# WiREDSchema.net
KiCad netlist of a schematic drawn in EAGLE
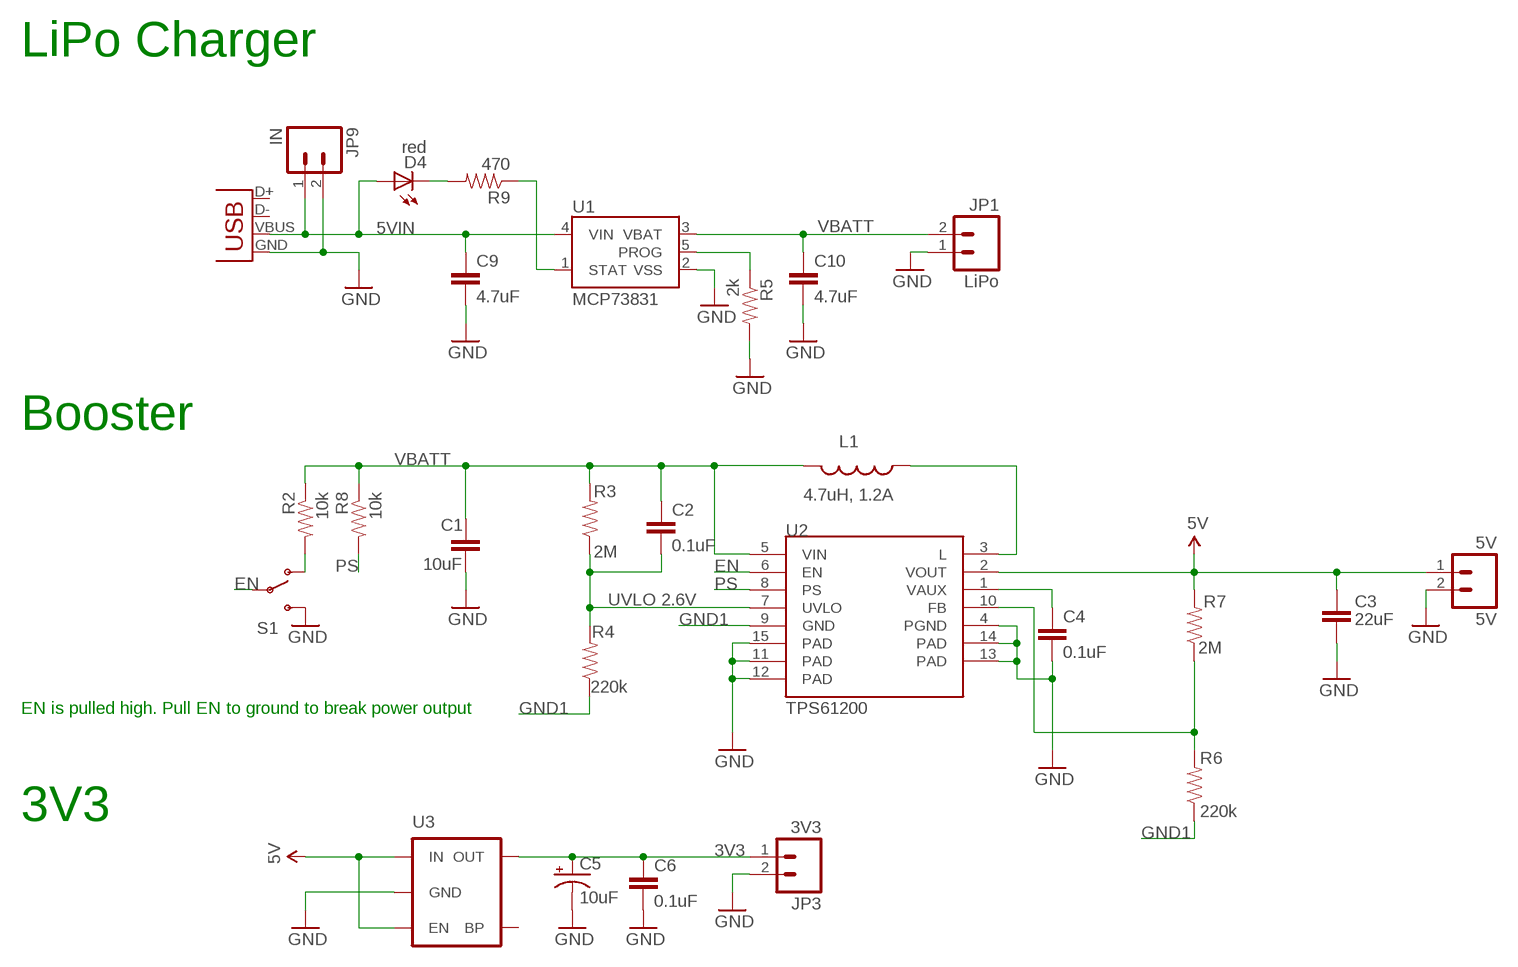
[diagram p0: schematic, sheet 1]

(export (version "E")
  (design (tool "Eeschema 10.0.6"))
  (components
    (comp (ref "5V")
      (value "5V")
      (footprint "eagle-import:1X02")
      (libsource (lib "eagle-import") (part "M02PTH"))
    )
    (comp (ref "C1")
      (value "10uF")
      (footprint "eagle-import:1206")
      (fields (field (name "MF") "AVX") (field (name "MPN") "12066D106KAT2A"))
      (libsource (lib "eagle-import") (part "CAP1206"))
    )
    (comp (ref "C2")
      (value "0.1uF")
      (footprint "eagle-import:0402-CAP")
      (fields (field (name "MF") "AVX") (field (name "MPN") "04026D104KAT2A"))
      (libsource (lib "eagle-import") (part "CAP0402-CAP"))
    )
    (comp (ref "C3")
      (value "22uF")
      (footprint "eagle-import:0805")
      (fields (field (name "MF") "KEMET") (field (name "MPN") "C0805C226M9PACTU"))
      (libsource (lib "eagle-import") (part "CAP0805"))
    )
    (comp (ref "C4")
      (value "0.1uF")
      (footprint "eagle-import:0402-CAP")
      (fields (field (name "MF") "AVX") (field (name "MPN") "04026D104KAT2A"))
      (libsource (lib "eagle-import") (part "CAP0402-CAP"))
    )
    (comp (ref "C5")
      (value "10uF")
      (footprint "eagle-import:EIA3216")
      (fields (field (name "MF") "AVX") (field (name "MPN") "TAJA106K006RNJ"))
      (libsource (lib "eagle-import") (part "10UF-16V-10%(TANT)"))
    )
    (comp (ref "C6")
      (value "0.1uF")
      (footprint "eagle-import:0402-CAP")
      (fields (field (name "MF") "AVX") (field (name "MPN") "04026D104KAT2A"))
      (libsource (lib "eagle-import") (part "CAP0402-CAP"))
    )
    (comp (ref "C9")
      (value "4.7uF")
      (footprint "eagle-import:0402-CAP")
      (fields (field (name "MF") "TAIYO YUDEN") (field (name "MPN") "JMK105BBJ475MV-F"))
      (libsource (lib "eagle-import") (part "CAP0402-CAP"))
    )
    (comp (ref "C10")
      (value "4.7uF")
      (footprint "eagle-import:0402-CAP")
      (fields (field (name "MF") "TAIYO YUDEN") (field (name "MPN") "JMK105BBJ475MV-F"))
      (libsource (lib "eagle-import") (part "CAP0402-CAP"))
    )
    (comp (ref "D4")
      (value "red")
      (footprint "eagle-import:LED-0603")
      (fields (field (name "MF") "VISHAY") (field (name "MPN") "TLMS1100-GS08."))
      (libsource (lib "eagle-import") (part "LED0603"))
    )
    (comp (ref "JP1")
      (value "LiPo")
      (footprint "eagle-import:JST-2-SMD")
      (libsource (lib "eagle-import") (part "M02-JST-2MM-SMT"))
    )
    (comp (ref "JP3")
      (value "3V3")
      (footprint "eagle-import:1X02")
      (libsource (lib "eagle-import") (part "M02PTH"))
    )
    (comp (ref "JP9")
      (value "IN")
      (footprint "eagle-import:1X02")
      (libsource (lib "eagle-import") (part "M02PTH"))
    )
    (comp (ref "L1")
      (value "4.7uH, 1.2A")
      (footprint "eagle-import:CDRH2D09")
      (fields (field (name "MF") "BOURNS") (field (name "MPN") "SRR4011-4R7YL"))
      (libsource (lib "eagle-import") (part "INDUCTOR."))
    )
    (comp (ref "R2")
      (value "10k")
      (footprint "eagle-import:0402-RES")
      (fields (field (name "MF") "TE CONNECTIVITY") (field (name "MPN") "CRG0402J10K"))
      (libsource (lib "eagle-import") (part "RESISTOR0402-RES"))
    )
    (comp (ref "R3")
      (value "2M")
      (footprint "eagle-import:0402-RES")
      (fields (field (name "MF") "PANASONIC") (field (name "MPN") "ERJ2GEJ205X"))
      (libsource (lib "eagle-import") (part "RESISTOR0402-RES"))
    )
    (comp (ref "R4")
      (value "220k")
      (footprint "eagle-import:0402-RES")
      (fields (field (name "MF") "PANASONIC") (field (name "MPN") "ERJ2GEJ224X"))
      (libsource (lib "eagle-import") (part "RESISTOR0402-RES"))
    )
    (comp (ref "R5")
      (value "2k")
      (footprint "eagle-import:0402-RES")
      (fields (field (name "MF") "PANASONIC") (field (name "MPN") "ERJ2RKF2001X"))
      (libsource (lib "eagle-import") (part "RESISTOR0402-RES"))
    )
    (comp (ref "R6")
      (value "220k")
      (footprint "eagle-import:0402-RES")
      (fields (field (name "MF") "PANASONIC") (field (name "MPN") "ERJ2GEJ224X"))
      (libsource (lib "eagle-import") (part "RESISTOR0402-RES"))
    )
    (comp (ref "R7")
      (value "2M")
      (footprint "eagle-import:0402-RES")
      (fields (field (name "MF") "PANASONIC") (field (name "MPN") "ERJ2GEJ205X"))
      (libsource (lib "eagle-import") (part "RESISTOR0402-RES"))
    )
    (comp (ref "R8")
      (value "10k")
      (footprint "eagle-import:0402-RES")
      (fields (field (name "MF") "TE CONNECTIVITY") (field (name "MPN") "CRG0402J10K"))
      (libsource (lib "eagle-import") (part "RESISTOR0402-RES"))
    )
    (comp (ref "R9")
      (value "470")
      (footprint "eagle-import:0402-RES")
      (fields (field (name "MF") "TE CONNECTIVITY") (field (name "MPN") "CRG0402F470R"))
      (libsource (lib "eagle-import") (part "RESISTOR0402-RES"))
    )
    (comp (ref "S1")
      (value "SWITCH-SPDTSMD")
      (footprint "eagle-import:AYZ0202")
      (libsource (lib "eagle-import") (part "SWITCH-SPDTSMD"))
    )
    (comp (ref "U1")
      (value "MCP73831")
      (footprint "eagle-import:SOT23-5")
      (fields (field (name "MF") "MICROCHIP") (field (name "MPN") "MCP73831T-2ACI/OT"))
      (libsource (lib "eagle-import") (part "MCP73831"))
    )
    (comp (ref "U2")
      (value "TPS61200")
      (footprint "eagle-import:QFN-10_PAD")
      (fields (field (name "MF") "TEXAS INSTRUMENTS") (field (name "MPN") "TPS61200DRCTG4"))
      (libsource (lib "eagle-import") (part "TPS61200"))
    )
    (comp (ref "U3")
      (value "MIC52053.3V")
      (footprint "eagle-import:SOT23-5")
      (fields (field (name "MF") "MICREL SEMICONDUCTOR") (field (name "MPN") "MIC5205YM5 TR"))
      (libsource (lib "eagle-import") (part "MIC52053.3V"))
    )
    (comp (ref "X1")
      (value "USB-MICROB")
      (footprint "eagle-import:USB-MICROB")
      (libsource (lib "eagle-import") (part "USB-MICROB"))
    )
  )
  (nets
    (net (code "1") (name "/3V3") (class "Default")
      (node (ref "C5") (pin "A") (pinfunction "+_A") (pintype "passive"))
      (node (ref "C6") (pin "1") (pinfunction "1_1") (pintype "passive"))
      (node (ref "JP3") (pin "1") (pinfunction "1_1") (pintype "passive"))
      (node (ref "U3") (pin "5") (pinfunction "OUT_5") (pintype "passive"))
    )
    (net (code "2") (name "/5VIN") (class "Default")
      (node (ref "C9") (pin "1") (pinfunction "1_1") (pintype "passive"))
      (node (ref "D4") (pin "A") (pinfunction "A_A") (pintype "passive"))
      (node (ref "JP9") (pin "1") (pinfunction "1_1") (pintype "passive"))
      (node (ref "U1") (pin "4") (pinfunction "VIN_4") (pintype "power_in"))
      (node (ref "X1") (pin "VBUS") (pinfunction "VBUS_VBUS") (pintype "bidirectional"))
    )
    (net (code "3") (name "/EN") (class "Default")
      (node (ref "S1") (pin "2") (pinfunction "P_2") (pintype "passive"))
      (node (ref "U2") (pin "6") (pinfunction "EN_6") (pintype "input"))
    )
    (net (code "4") (name "/GND1") (class "Default")
      (node (ref "R4") (pin "1") (pinfunction "1_1") (pintype "passive"))
      (node (ref "R6") (pin "1") (pinfunction "1_1") (pintype "passive"))
      (node (ref "U2") (pin "9") (pinfunction "GND_9") (pintype "power_in"))
    )
    (net (code "5") (name "/PS") (class "Default")
      (node (ref "R8") (pin "2") (pinfunction "2_2") (pintype "passive"))
      (node (ref "U2") (pin "8") (pinfunction "PS_8") (pintype "input"))
    )
    (net (code "6") (name "/VBATT") (class "Default")
      (node (ref "C1") (pin "1") (pinfunction "1_1") (pintype "passive"))
      (node (ref "C10") (pin "1") (pinfunction "1_1") (pintype "passive"))
      (node (ref "C2") (pin "1") (pinfunction "1_1") (pintype "passive"))
      (node (ref "JP1") (pin "2") (pinfunction "2_2") (pintype "passive"))
      (node (ref "L1") (pin "P$2") (pinfunction "2_P$2") (pintype "passive"))
      (node (ref "R2") (pin "1") (pinfunction "1_1") (pintype "passive"))
      (node (ref "R3") (pin "2") (pinfunction "2_2") (pintype "passive"))
      (node (ref "R8") (pin "1") (pinfunction "1_1") (pintype "passive"))
      (node (ref "U1") (pin "3") (pinfunction "VBAT_3") (pintype "power_in"))
      (node (ref "U2") (pin "5") (pinfunction "VIN_5") (pintype "power_in"))
    )
    (net (code "7") (name "5V") (class "Default")
      (node (ref "5V") (pin "1") (pinfunction "1_1") (pintype "passive"))
      (node (ref "C3") (pin "1") (pinfunction "1_1") (pintype "passive"))
      (node (ref "R7") (pin "2") (pinfunction "2_2") (pintype "passive"))
      (node (ref "U2") (pin "2") (pinfunction "VOUT_2") (pintype "passive"))
      (node (ref "U3") (pin "1") (pinfunction "IN_1") (pintype "input"))
      (node (ref "U3") (pin "3") (pinfunction "EN_3") (pintype "input"))
    )
    (net (code "8") (name "GND") (class "Default")
      (node (ref "5V") (pin "2") (pinfunction "2_2") (pintype "passive"))
      (node (ref "C1") (pin "2") (pinfunction "2_2") (pintype "passive"))
      (node (ref "C10") (pin "2") (pinfunction "2_2") (pintype "passive"))
      (node (ref "C3") (pin "2") (pinfunction "2_2") (pintype "passive"))
      (node (ref "C4") (pin "2") (pinfunction "2_2") (pintype "passive"))
      (node (ref "C5") (pin "C") (pinfunction "-_C") (pintype "passive"))
      (node (ref "C6") (pin "2") (pinfunction "2_2") (pintype "passive"))
      (node (ref "C9") (pin "2") (pinfunction "2_2") (pintype "passive"))
      (node (ref "JP1") (pin "1") (pinfunction "1_1") (pintype "passive"))
      (node (ref "JP3") (pin "2") (pinfunction "2_2") (pintype "passive"))
      (node (ref "JP9") (pin "2") (pinfunction "2_2") (pintype "passive"))
      (node (ref "R5") (pin "2") (pinfunction "2_2") (pintype "passive"))
      (node (ref "S1") (pin "3") (pinfunction "S_3") (pintype "passive"))
      (node (ref "U1") (pin "2") (pinfunction "VSS_2") (pintype "power_in"))
      (node (ref "U2") (pin "11") (pinfunction "PAD_11") (pintype "power_in"))
      (node (ref "U2") (pin "12") (pinfunction "PAD_12") (pintype "power_in"))
      (node (ref "U2") (pin "13") (pinfunction "PAD_13") (pintype "power_in"))
      (node (ref "U2") (pin "14") (pinfunction "PAD_14") (pintype "power_in"))
      (node (ref "U2") (pin "15") (pinfunction "PAD_15") (pintype "power_in"))
      (node (ref "U2") (pin "4") (pinfunction "PGND_4") (pintype "power_in"))
      (node (ref "U3") (pin "2") (pinfunction "GND_2") (pintype "input"))
      (node (ref "X1") (pin "GND") (pinfunction "GND_GND") (pintype "bidirectional"))
    )
    (net (code "9") (name "Net-(D4-PadC)") (class "Default")
      (node (ref "D4") (pin "C") (pinfunction "C_C") (pintype "passive"))
      (node (ref "R9") (pin "2") (pinfunction "2_2") (pintype "passive"))
    )
    (net (code "10") (name "Net-(L1-1)") (class "Default")
      (node (ref "L1") (pin "P$1") (pinfunction "1_P$1") (pintype "passive"))
      (node (ref "U2") (pin "3") (pinfunction "L_3") (pintype "passive"))
    )
    (net (code "11") (name "Net-(S1-O)") (class "Default")
      (node (ref "R2") (pin "2") (pinfunction "2_2") (pintype "passive"))
      (node (ref "S1") (pin "1") (pinfunction "O_1") (pintype "passive"))
    )
    (net (code "12") (name "Net-(U1-PROG)") (class "Default")
      (node (ref "R5") (pin "1") (pinfunction "1_1") (pintype "passive"))
      (node (ref "U1") (pin "5") (pinfunction "PROG_5") (pintype "input"))
    )
    (net (code "13") (name "Net-(U1-STAT)") (class "Default")
      (node (ref "R9") (pin "1") (pinfunction "1_1") (pintype "passive"))
      (node (ref "U1") (pin "1") (pinfunction "STAT_1") (pintype "output"))
    )
    (net (code "14") (name "Net-(U2-FB)") (class "Default")
      (node (ref "R6") (pin "2") (pinfunction "2_2") (pintype "passive"))
      (node (ref "R7") (pin "1") (pinfunction "1_1") (pintype "passive"))
      (node (ref "U2") (pin "10") (pinfunction "FB_10") (pintype "passive"))
    )
    (net (code "15") (name "Net-(U2-UVLO)") (class "Default")
      (node (ref "C2") (pin "2") (pinfunction "2_2") (pintype "passive"))
      (node (ref "R3") (pin "1") (pinfunction "1_1") (pintype "passive"))
      (node (ref "R4") (pin "2") (pinfunction "2_2") (pintype "passive"))
      (node (ref "U2") (pin "7") (pinfunction "UVLO_7") (pintype "passive"))
    )
    (net (code "16") (name "Net-(U2-VAUX)") (class "Default")
      (node (ref "C4") (pin "1") (pinfunction "1_1") (pintype "passive"))
      (node (ref "U2") (pin "1") (pinfunction "VAUX_1") (pintype "passive"))
    )
    (net (code "17") (name "unconnected-(U3-BP-Pad4)") (class "Default")
      (node (ref "U3") (pin "4") (pinfunction "BP_4") (pintype "input"))
    )
    (net (code "18") (name "unconnected-(X1-PadD+)") (class "Default")
      (node (ref "X1") (pin "D+") (pinfunction "D+_D+") (pintype "bidirectional"))
    )
    (net (code "19") (name "unconnected-(X1-PadD-)") (class "Default")
      (node (ref "X1") (pin "D-") (pinfunction "D-_D-") (pintype "bidirectional"))
    )
  )
)
